# eMMC.net
KiCad netlist of a schematic drawn in Altium Designer
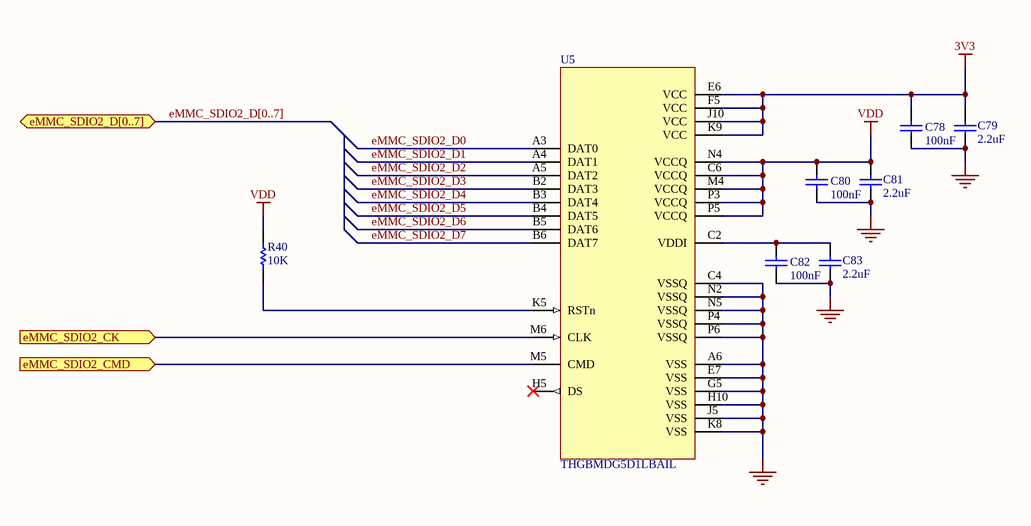
[diagram p0: eMMC.SchDoc]

(export (version "E")
  (design (tool "Eeschema 10.0.6"))
  (components
    (comp (ref "C78")
      (value "100nF")
      (footprint "C0402")
      (description "Capacitor, MLCC, 100nF, 16V, X7R, 10%, 0402, T=0.5mm")
      (fields
        (field (name "INTERNAL_PART_NUMBER") "MCD-00006")
        (field (name "MANUFACTURER_PART_NUMBER") "CC0402KRX7R7BB104")
        (field (name "PROVIDED_BY") "SUBCO")
      )
      (libsource (lib "MCD_PARTS_database") (part "Capacitor"))
    )
    (comp (ref "C79")
      (value "2.2uF")
      (footprint "C0603")
      (description "Capacitor, MLCC, 2.2uF, 10V, X5R, 10%, 0603, T=0,8mm")
      (fields
        (field (name "INTERNAL_PART_NUMBER") "MCD-00012")
        (field (name "MANUFACTURER_PART_NUMBER") "CC0603KRX5R6BB225")
        (field (name "PROVIDED_BY") "SUBCO")
      )
      (libsource (lib "MCD_PARTS_database") (part "Capacitor"))
    )
    (comp (ref "C80")
      (value "100nF")
      (footprint "C0402")
      (description "Capacitor, MLCC, 100nF, 16V, X7R, 10%, 0402, T=0.5mm")
      (fields
        (field (name "INTERNAL_PART_NUMBER") "MCD-00006")
        (field (name "MANUFACTURER_PART_NUMBER") "CC0402KRX7R7BB104")
        (field (name "PROVIDED_BY") "SUBCO")
      )
      (libsource (lib "MCD_PARTS_database") (part "Capacitor"))
    )
    (comp (ref "C81")
      (value "2.2uF")
      (footprint "C0603")
      (description "Capacitor, MLCC, 2.2uF, 10V, X5R, 10%, 0603, T=0,8mm")
      (fields
        (field (name "INTERNAL_PART_NUMBER") "MCD-00012")
        (field (name "MANUFACTURER_PART_NUMBER") "CC0603KRX5R6BB225")
        (field (name "PROVIDED_BY") "SUBCO")
      )
      (libsource (lib "MCD_PARTS_database") (part "Capacitor"))
    )
    (comp (ref "C82")
      (value "100nF")
      (footprint "C0402")
      (description "Capacitor, MLCC, 100nF, 16V, X7R, 10%, 0402, T=0.5mm")
      (fields
        (field (name "INTERNAL_PART_NUMBER") "MCD-00006")
        (field (name "MANUFACTURER_PART_NUMBER") "CC0402KRX7R7BB104")
        (field (name "PROVIDED_BY") "SUBCO")
      )
      (libsource (lib "MCD_PARTS_database") (part "Capacitor"))
    )
    (comp (ref "C83")
      (value "2.2uF")
      (footprint "C0603")
      (description "Capacitor, MLCC, 2.2uF, 10V, X5R, 10%, 0603, T=0,8mm")
      (fields
        (field (name "INTERNAL_PART_NUMBER") "MCD-00012")
        (field (name "MANUFACTURER_PART_NUMBER") "CC0603KRX5R6BB225")
        (field (name "PROVIDED_BY") "SUBCO")
      )
      (libsource (lib "MCD_PARTS_database") (part "Capacitor"))
    )
    (comp (ref "R40")
      (value "10K")
      (footprint "R0402")
      (description "Resistor,10K,0402,1%,1/16W")
      (fields
        (field (name "INTERNAL_PART_NUMBER") "MCD-00053")
        (field (name "MANUFACTURER_PART_NUMBER") "RC0402FR-0710KL")
        (field (name "PROVIDED_BY") "SUBCO")
      )
      (libsource (lib "MCD_PARTS_database") (part "Resistor"))
    )
    (comp (ref "U5")
      (value "THGBMDG5D1LBAIL")
      (footprint "ICC_P-WFBGA153_13X11P5_P050")
      (description "Memory,e-MMC,4GB,3V3,WFBGA,153pins")
      (fields
        (field (name "INTERNAL_PART_NUMBER") "MCD-00110")
        (field (name "MANUFACTURER") "TOSHIBA")
        (field (name "PROVIDED_BY") "SUBCO")
      )
      (libsource (lib "MCD_PARTS_database") (part "eMMC_THGBMDG5D1LBAIL"))
    )
  )
  (nets
    (net (code "1") (name "/eMMC_SDIO2_CK") (class "Default")
      (node (ref "U5") (pin "M6") (pinfunction "CLK_M6") (pintype "input"))
    )
    (net (code "2") (name "/eMMC_SDIO2_CMD") (class "Default")
      (node (ref "U5") (pin "M5") (pinfunction "CMD_M5") (pintype "passive"))
    )
    (net (code "3") (name "/eMMC_SDIO2_D0") (class "Default")
      (node (ref "U5") (pin "A3") (pinfunction "DAT0_A3") (pintype "passive"))
    )
    (net (code "4") (name "/eMMC_SDIO2_D1") (class "Default")
      (node (ref "U5") (pin "A4") (pinfunction "DAT1_A4") (pintype "passive"))
    )
    (net (code "5") (name "/eMMC_SDIO2_D2") (class "Default")
      (node (ref "U5") (pin "A5") (pinfunction "DAT2_A5") (pintype "passive"))
    )
    (net (code "6") (name "/eMMC_SDIO2_D3") (class "Default")
      (node (ref "U5") (pin "B2") (pinfunction "DAT3_B2") (pintype "passive"))
    )
    (net (code "7") (name "/eMMC_SDIO2_D4") (class "Default")
      (node (ref "U5") (pin "B3") (pinfunction "DAT4_B3") (pintype "passive"))
    )
    (net (code "8") (name "/eMMC_SDIO2_D5") (class "Default")
      (node (ref "U5") (pin "B4") (pinfunction "DAT5_B4") (pintype "passive"))
    )
    (net (code "9") (name "/eMMC_SDIO2_D6") (class "Default")
      (node (ref "U5") (pin "B5") (pinfunction "DAT6_B5") (pintype "passive"))
    )
    (net (code "10") (name "/eMMC_SDIO2_D7") (class "Default")
      (node (ref "U5") (pin "B6") (pinfunction "DAT7_B6") (pintype "passive"))
    )
    (net (code "12") (name "3V3") (class "Default")
      (node (ref "C78") (pin "2") (pinfunction "2_2") (pintype "passive"))
      (node (ref "C79") (pin "2") (pinfunction "2_2") (pintype "passive"))
      (node (ref "U5") (pin "E6") (pinfunction "VCC_E6") (pintype "passive"))
      (node (ref "U5") (pin "F5") (pinfunction "VCC_F5") (pintype "passive"))
      (node (ref "U5") (pin "J10") (pinfunction "VCC_J10") (pintype "passive"))
      (node (ref "U5") (pin "K9") (pinfunction "VCC_K9") (pintype "passive"))
    )
    (net (code "13") (name "GND") (class "Default")
      (node (ref "C78") (pin "1") (pinfunction "1_1") (pintype "passive"))
      (node (ref "C79") (pin "1") (pinfunction "1_1") (pintype "passive"))
      (node (ref "C80") (pin "1") (pinfunction "1_1") (pintype "passive"))
      (node (ref "C81") (pin "1") (pinfunction "1_1") (pintype "passive"))
      (node (ref "C82") (pin "1") (pinfunction "1_1") (pintype "passive"))
      (node (ref "C83") (pin "1") (pinfunction "1_1") (pintype "passive"))
      (node (ref "U5") (pin "A6") (pinfunction "VSS_A6") (pintype "passive"))
      (node (ref "U5") (pin "C4") (pinfunction "VSSQ_C4") (pintype "passive"))
      (node (ref "U5") (pin "E7") (pinfunction "VSS_E7") (pintype "passive"))
      (node (ref "U5") (pin "G5") (pinfunction "VSS_G5") (pintype "passive"))
      (node (ref "U5") (pin "H10") (pinfunction "VSS_H10") (pintype "passive"))
      (node (ref "U5") (pin "J5") (pinfunction "VSS_J5") (pintype "passive"))
      (node (ref "U5") (pin "K8") (pinfunction "VSS_K8") (pintype "passive"))
      (node (ref "U5") (pin "N2") (pinfunction "VSSQ_N2") (pintype "passive"))
      (node (ref "U5") (pin "N5") (pinfunction "VSSQ_N5") (pintype "passive"))
      (node (ref "U5") (pin "P4") (pinfunction "VSSQ_P4") (pintype "passive"))
      (node (ref "U5") (pin "P6") (pinfunction "VSSQ_P6") (pintype "passive"))
    )
    (net (code "14") (name "Net-(U5-RSTn)") (class "Default")
      (node (ref "R40") (pin "1") (pinfunction "1_1") (pintype "passive"))
      (node (ref "U5") (pin "K5") (pinfunction "RSTn_K5") (pintype "input"))
    )
    (net (code "15") (name "Net-(U5-VDDI)") (class "Default")
      (node (ref "C82") (pin "2") (pinfunction "2_2") (pintype "passive"))
      (node (ref "C83") (pin "2") (pinfunction "2_2") (pintype "passive"))
      (node (ref "U5") (pin "C2") (pinfunction "VDDI_C2") (pintype "passive"))
    )
    (net (code "16") (name "VDD") (class "Default")
      (node (ref "C80") (pin "2") (pinfunction "2_2") (pintype "passive"))
      (node (ref "C81") (pin "2") (pinfunction "2_2") (pintype "passive"))
      (node (ref "R40") (pin "2") (pinfunction "2_2") (pintype "passive"))
      (node (ref "U5") (pin "C6") (pinfunction "VCCQ_C6") (pintype "passive"))
      (node (ref "U5") (pin "M4") (pinfunction "VCCQ_M4") (pintype "passive"))
      (node (ref "U5") (pin "N4") (pinfunction "VCCQ_N4") (pintype "passive"))
      (node (ref "U5") (pin "P3") (pinfunction "VCCQ_P3") (pintype "passive"))
      (node (ref "U5") (pin "P5") (pinfunction "VCCQ_P5") (pintype "passive"))
    )
    (net (code "17") (name "unconnected-(U5-DS-PadH5)") (class "Default")
      (node (ref "U5") (pin "H5") (pinfunction "DS_H5") (pintype "output+no_connect"))
    )
  )
)
